# IOIOShield.net
KiCad netlist of a schematic drawn in EAGLE
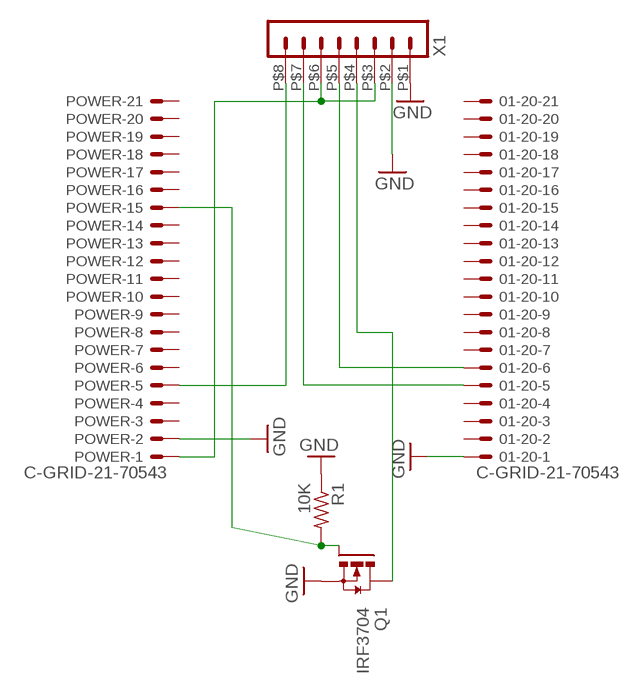
[diagram p0: schematic, sheet 1]

(export (version "E")
  (design (tool "Eeschema 10.0.6"))
  (components
    (comp (ref "01-20")
      (value "C-GRID-21-70543")
      (footprint "eagle-import:70543-21")
      (libsource (lib "eagle-import") (part "C-GRID-21-70543"))
    )
    (comp (ref "POWER")
      (value "C-GRID-21-70543")
      (footprint "eagle-import:70543-21")
      (libsource (lib "eagle-import") (part "C-GRID-21-70543"))
    )
    (comp (ref "Q1")
      (value "IRF3704")
      (footprint "eagle-import:TO220AH")
      (libsource (lib "eagle-import") (part "IRF3704"))
    )
    (comp (ref "R1")
      (value "10K")
      (footprint "eagle-import:0204_7")
      (libsource (lib "eagle-import") (part "R-US_0204/7"))
    )
    (comp (ref "X1")
      (value "HEADER_POS8_43045-0800")
      (footprint "eagle-import:43045-0800")
      (libsource (lib "eagle-import") (part "HEADER_POS8_?43045-0800"))
    )
  )
  (nets
    (net (code "1") (name "GND") (class "Default")
      (node (ref "01-20") (pin "1") (pinfunction "S_1") (pintype "passive"))
      (node (ref "POWER") (pin "2") (pinfunction "S_2") (pintype "passive"))
      (node (ref "Q1") (pin "E") (pinfunction "S_E") (pintype "passive"))
      (node (ref "R1") (pin "1") (pinfunction "1_1") (pintype "passive"))
      (node (ref "X1") (pin "P$1") (pinfunction "1_P$1") (pintype "passive"))
      (node (ref "X1") (pin "P$2") (pinfunction "2_P$2") (pintype "passive"))
    )
    (net (code "2") (name "Net-(01-20Q-S)") (class "Default")
      (node (ref "01-20") (pin "5") (pinfunction "S_5") (pintype "passive"))
      (node (ref "X1") (pin "P$7") (pinfunction "7_P$7") (pintype "passive"))
    )
    (net (code "3") (name "Net-(01-20R-S)") (class "Default")
      (node (ref "01-20") (pin "6") (pinfunction "S_6") (pintype "passive"))
      (node (ref "X1") (pin "P$5") (pinfunction "5_P$5") (pintype "passive"))
    )
    (net (code "4") (name "Net-(POWERA-S)") (class "Default")
      (node (ref "POWER") (pin "1") (pinfunction "S_1") (pintype "passive"))
      (node (ref "X1") (pin "P$3") (pinfunction "3_P$3") (pintype "passive"))
      (node (ref "X1") (pin "P$6") (pinfunction "6_P$6") (pintype "passive"))
    )
    (net (code "5") (name "Net-(POWERG-S)") (class "Default")
      (node (ref "POWER") (pin "15") (pinfunction "S_15") (pintype "passive"))
      (node (ref "Q1") (pin "B") (pinfunction "G_B") (pintype "passive"))
      (node (ref "R1") (pin "2") (pinfunction "2_2") (pintype "passive"))
    )
    (net (code "6") (name "Net-(POWERQ-S)") (class "Default")
      (node (ref "POWER") (pin "5") (pinfunction "S_5") (pintype "passive"))
      (node (ref "X1") (pin "P$8") (pinfunction "8_P$8") (pintype "passive"))
    )
    (net (code "7") (name "Net-(Q1-D)") (class "Default")
      (node (ref "Q1") (pin "C") (pinfunction "D_C") (pintype "passive"))
      (node (ref "X1") (pin "P$4") (pinfunction "4_P$4") (pintype "passive"))
    )
    (net (code "8") (name "unconnected-(01-20B-S-Pad10)") (class "Default")
      (node (ref "01-20") (pin "10") (pinfunction "S_10") (pintype "passive"))
    )
    (net (code "9") (name "unconnected-(01-20C-S-Pad11)") (class "Default")
      (node (ref "01-20") (pin "11") (pinfunction "S_11") (pintype "passive"))
    )
    (net (code "10") (name "unconnected-(01-20D-S-Pad12)") (class "Default")
      (node (ref "01-20") (pin "12") (pinfunction "S_12") (pintype "passive"))
    )
    (net (code "11") (name "unconnected-(01-20E-S-Pad13)") (class "Default")
      (node (ref "01-20") (pin "13") (pinfunction "S_13") (pintype "passive"))
    )
    (net (code "12") (name "unconnected-(01-20F-S-Pad14)") (class "Default")
      (node (ref "01-20") (pin "14") (pinfunction "S_14") (pintype "passive"))
    )
    (net (code "13") (name "unconnected-(01-20G-S-Pad15)") (class "Default")
      (node (ref "01-20") (pin "15") (pinfunction "S_15") (pintype "passive"))
    )
    (net (code "14") (name "unconnected-(01-20H-S-Pad16)") (class "Default")
      (node (ref "01-20") (pin "16") (pinfunction "S_16") (pintype "passive"))
    )
    (net (code "15") (name "unconnected-(01-20I-S-Pad17)") (class "Default")
      (node (ref "01-20") (pin "17") (pinfunction "S_17") (pintype "passive"))
    )
    (net (code "16") (name "unconnected-(01-20J-S-Pad18)") (class "Default")
      (node (ref "01-20") (pin "18") (pinfunction "S_18") (pintype "passive"))
    )
    (net (code "17") (name "unconnected-(01-20K-S-Pad19)") (class "Default")
      (node (ref "01-20") (pin "19") (pinfunction "S_19") (pintype "passive"))
    )
    (net (code "18") (name "unconnected-(01-20L-S-Pad2)") (class "Default")
      (node (ref "01-20") (pin "2") (pinfunction "S_2") (pintype "passive"))
    )
    (net (code "19") (name "unconnected-(01-20M-S-Pad20)") (class "Default")
      (node (ref "01-20") (pin "20") (pinfunction "S_20") (pintype "passive"))
    )
    (net (code "20") (name "unconnected-(01-20N-S-Pad21)") (class "Default")
      (node (ref "01-20") (pin "21") (pinfunction "S_21") (pintype "passive"))
    )
    (net (code "21") (name "unconnected-(01-20O-S-Pad3)") (class "Default")
      (node (ref "01-20") (pin "3") (pinfunction "S_3") (pintype "passive"))
    )
    (net (code "22") (name "unconnected-(01-20P-S-Pad4)") (class "Default")
      (node (ref "01-20") (pin "4") (pinfunction "S_4") (pintype "passive"))
    )
    (net (code "23") (name "unconnected-(01-20S-S-Pad7)") (class "Default")
      (node (ref "01-20") (pin "7") (pinfunction "S_7") (pintype "passive"))
    )
    (net (code "24") (name "unconnected-(01-20T-S-Pad8)") (class "Default")
      (node (ref "01-20") (pin "8") (pinfunction "S_8") (pintype "passive"))
    )
    (net (code "25") (name "unconnected-(01-20U-S-Pad9)") (class "Default")
      (node (ref "01-20") (pin "9") (pinfunction "S_9") (pintype "passive"))
    )
    (net (code "26") (name "unconnected-(POWERB-S-Pad10)") (class "Default")
      (node (ref "POWER") (pin "10") (pinfunction "S_10") (pintype "passive"))
    )
    (net (code "27") (name "unconnected-(POWERC-S-Pad11)") (class "Default")
      (node (ref "POWER") (pin "11") (pinfunction "S_11") (pintype "passive"))
    )
    (net (code "28") (name "unconnected-(POWERD-S-Pad12)") (class "Default")
      (node (ref "POWER") (pin "12") (pinfunction "S_12") (pintype "passive"))
    )
    (net (code "29") (name "unconnected-(POWERE-S-Pad13)") (class "Default")
      (node (ref "POWER") (pin "13") (pinfunction "S_13") (pintype "passive"))
    )
    (net (code "30") (name "unconnected-(POWERF-S-Pad14)") (class "Default")
      (node (ref "POWER") (pin "14") (pinfunction "S_14") (pintype "passive"))
    )
    (net (code "31") (name "unconnected-(POWERH-S-Pad16)") (class "Default")
      (node (ref "POWER") (pin "16") (pinfunction "S_16") (pintype "passive"))
    )
    (net (code "32") (name "unconnected-(POWERI-S-Pad17)") (class "Default")
      (node (ref "POWER") (pin "17") (pinfunction "S_17") (pintype "passive"))
    )
    (net (code "33") (name "unconnected-(POWERJ-S-Pad18)") (class "Default")
      (node (ref "POWER") (pin "18") (pinfunction "S_18") (pintype "passive"))
    )
    (net (code "34") (name "unconnected-(POWERK-S-Pad19)") (class "Default")
      (node (ref "POWER") (pin "19") (pinfunction "S_19") (pintype "passive"))
    )
    (net (code "35") (name "unconnected-(POWERM-S-Pad20)") (class "Default")
      (node (ref "POWER") (pin "20") (pinfunction "S_20") (pintype "passive"))
    )
    (net (code "36") (name "unconnected-(POWERN-S-Pad21)") (class "Default")
      (node (ref "POWER") (pin "21") (pinfunction "S_21") (pintype "passive"))
    )
    (net (code "37") (name "unconnected-(POWERO-S-Pad3)") (class "Default")
      (node (ref "POWER") (pin "3") (pinfunction "S_3") (pintype "passive"))
    )
    (net (code "38") (name "unconnected-(POWERP-S-Pad4)") (class "Default")
      (node (ref "POWER") (pin "4") (pinfunction "S_4") (pintype "passive"))
    )
    (net (code "39") (name "unconnected-(POWERR-S-Pad6)") (class "Default")
      (node (ref "POWER") (pin "6") (pinfunction "S_6") (pintype "passive"))
    )
    (net (code "40") (name "unconnected-(POWERS-S-Pad7)") (class "Default")
      (node (ref "POWER") (pin "7") (pinfunction "S_7") (pintype "passive"))
    )
    (net (code "41") (name "unconnected-(POWERT-S-Pad8)") (class "Default")
      (node (ref "POWER") (pin "8") (pinfunction "S_8") (pintype "passive"))
    )
    (net (code "42") (name "unconnected-(POWERU-S-Pad9)") (class "Default")
      (node (ref "POWER") (pin "9") (pinfunction "S_9") (pintype "passive"))
    )
  )
)
